# NRF24L01_Module_AnTenna_SMD_0603.net
KiCad netlist of a schematic drawn in EAGLE
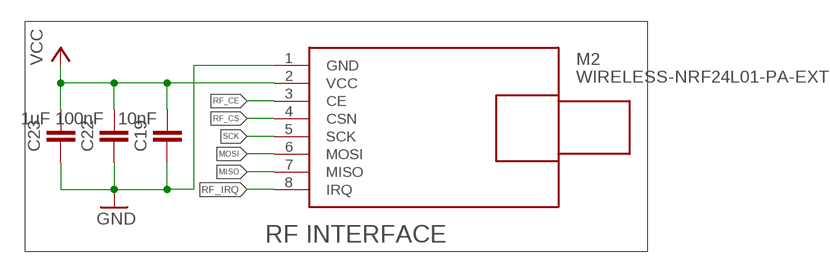
[diagram p0: schematic, sheet 1]

(export (version "E")
  (design (tool "Eeschema 10.0.6"))
  (components
    (comp (ref "C19")
      (value "10nF")
      (footprint "eagle-import:C0603")
      (libsource (lib "eagle-import") (part "C-EUC0603"))
    )
    (comp (ref "C22")
      (value "100nF")
      (footprint "eagle-import:C0603")
      (libsource (lib "eagle-import") (part "C-EUC0603"))
    )
    (comp (ref "C23")
      (value "1uF")
      (footprint "eagle-import:C0603")
      (libsource (lib "eagle-import") (part "C-EUC0603"))
    )
    (comp (ref "M2")
      (value "WIRELESS-NRF24L01-PA-EXT")
      (footprint "eagle-import:WIRELESS-NRF24L01-PA-EXT")
      (libsource (lib "eagle-import") (part "WIRELESS-NRF24L01-PA-EXT"))
    )
  )
  (nets
    (net (code "1") (name "GND") (class "Default")
      (node (ref "C19") (pin "1") (pinfunction "1_1") (pintype "passive"))
      (node (ref "C22") (pin "1") (pinfunction "1_1") (pintype "passive"))
      (node (ref "C23") (pin "1") (pinfunction "1_1") (pintype "passive"))
      (node (ref "M2") (pin "1") (pinfunction "GND_1") (pintype "power_in"))
    )
    (net (code "2") (name "MISO") (class "Default")
      (node (ref "M2") (pin "7") (pinfunction "MISO_7") (pintype "bidirectional"))
    )
    (net (code "3") (name "MOSI") (class "Default")
      (node (ref "M2") (pin "6") (pinfunction "MOSI_6") (pintype "bidirectional"))
    )
    (net (code "4") (name "RF_CE") (class "Default")
      (node (ref "M2") (pin "3") (pinfunction "CE_3") (pintype "bidirectional"))
    )
    (net (code "5") (name "RF_CS") (class "Default")
      (node (ref "M2") (pin "4") (pinfunction "CSN_4") (pintype "bidirectional"))
    )
    (net (code "6") (name "RF_IRQ") (class "Default")
      (node (ref "M2") (pin "8") (pinfunction "IRQ_8") (pintype "bidirectional"))
    )
    (net (code "7") (name "SCK") (class "Default")
      (node (ref "M2") (pin "5") (pinfunction "SCK_5") (pintype "bidirectional"))
    )
    (net (code "8") (name "VCC") (class "Default")
      (node (ref "C19") (pin "2") (pinfunction "2_2") (pintype "passive"))
      (node (ref "C22") (pin "2") (pinfunction "2_2") (pintype "passive"))
      (node (ref "C23") (pin "2") (pinfunction "2_2") (pintype "passive"))
      (node (ref "M2") (pin "2") (pinfunction "VCC_2") (pintype "power_in"))
    )
  )
)
